# Moter_Control_2021-08-13.net
KiCad netlist of a schematic drawn in Altium Designer
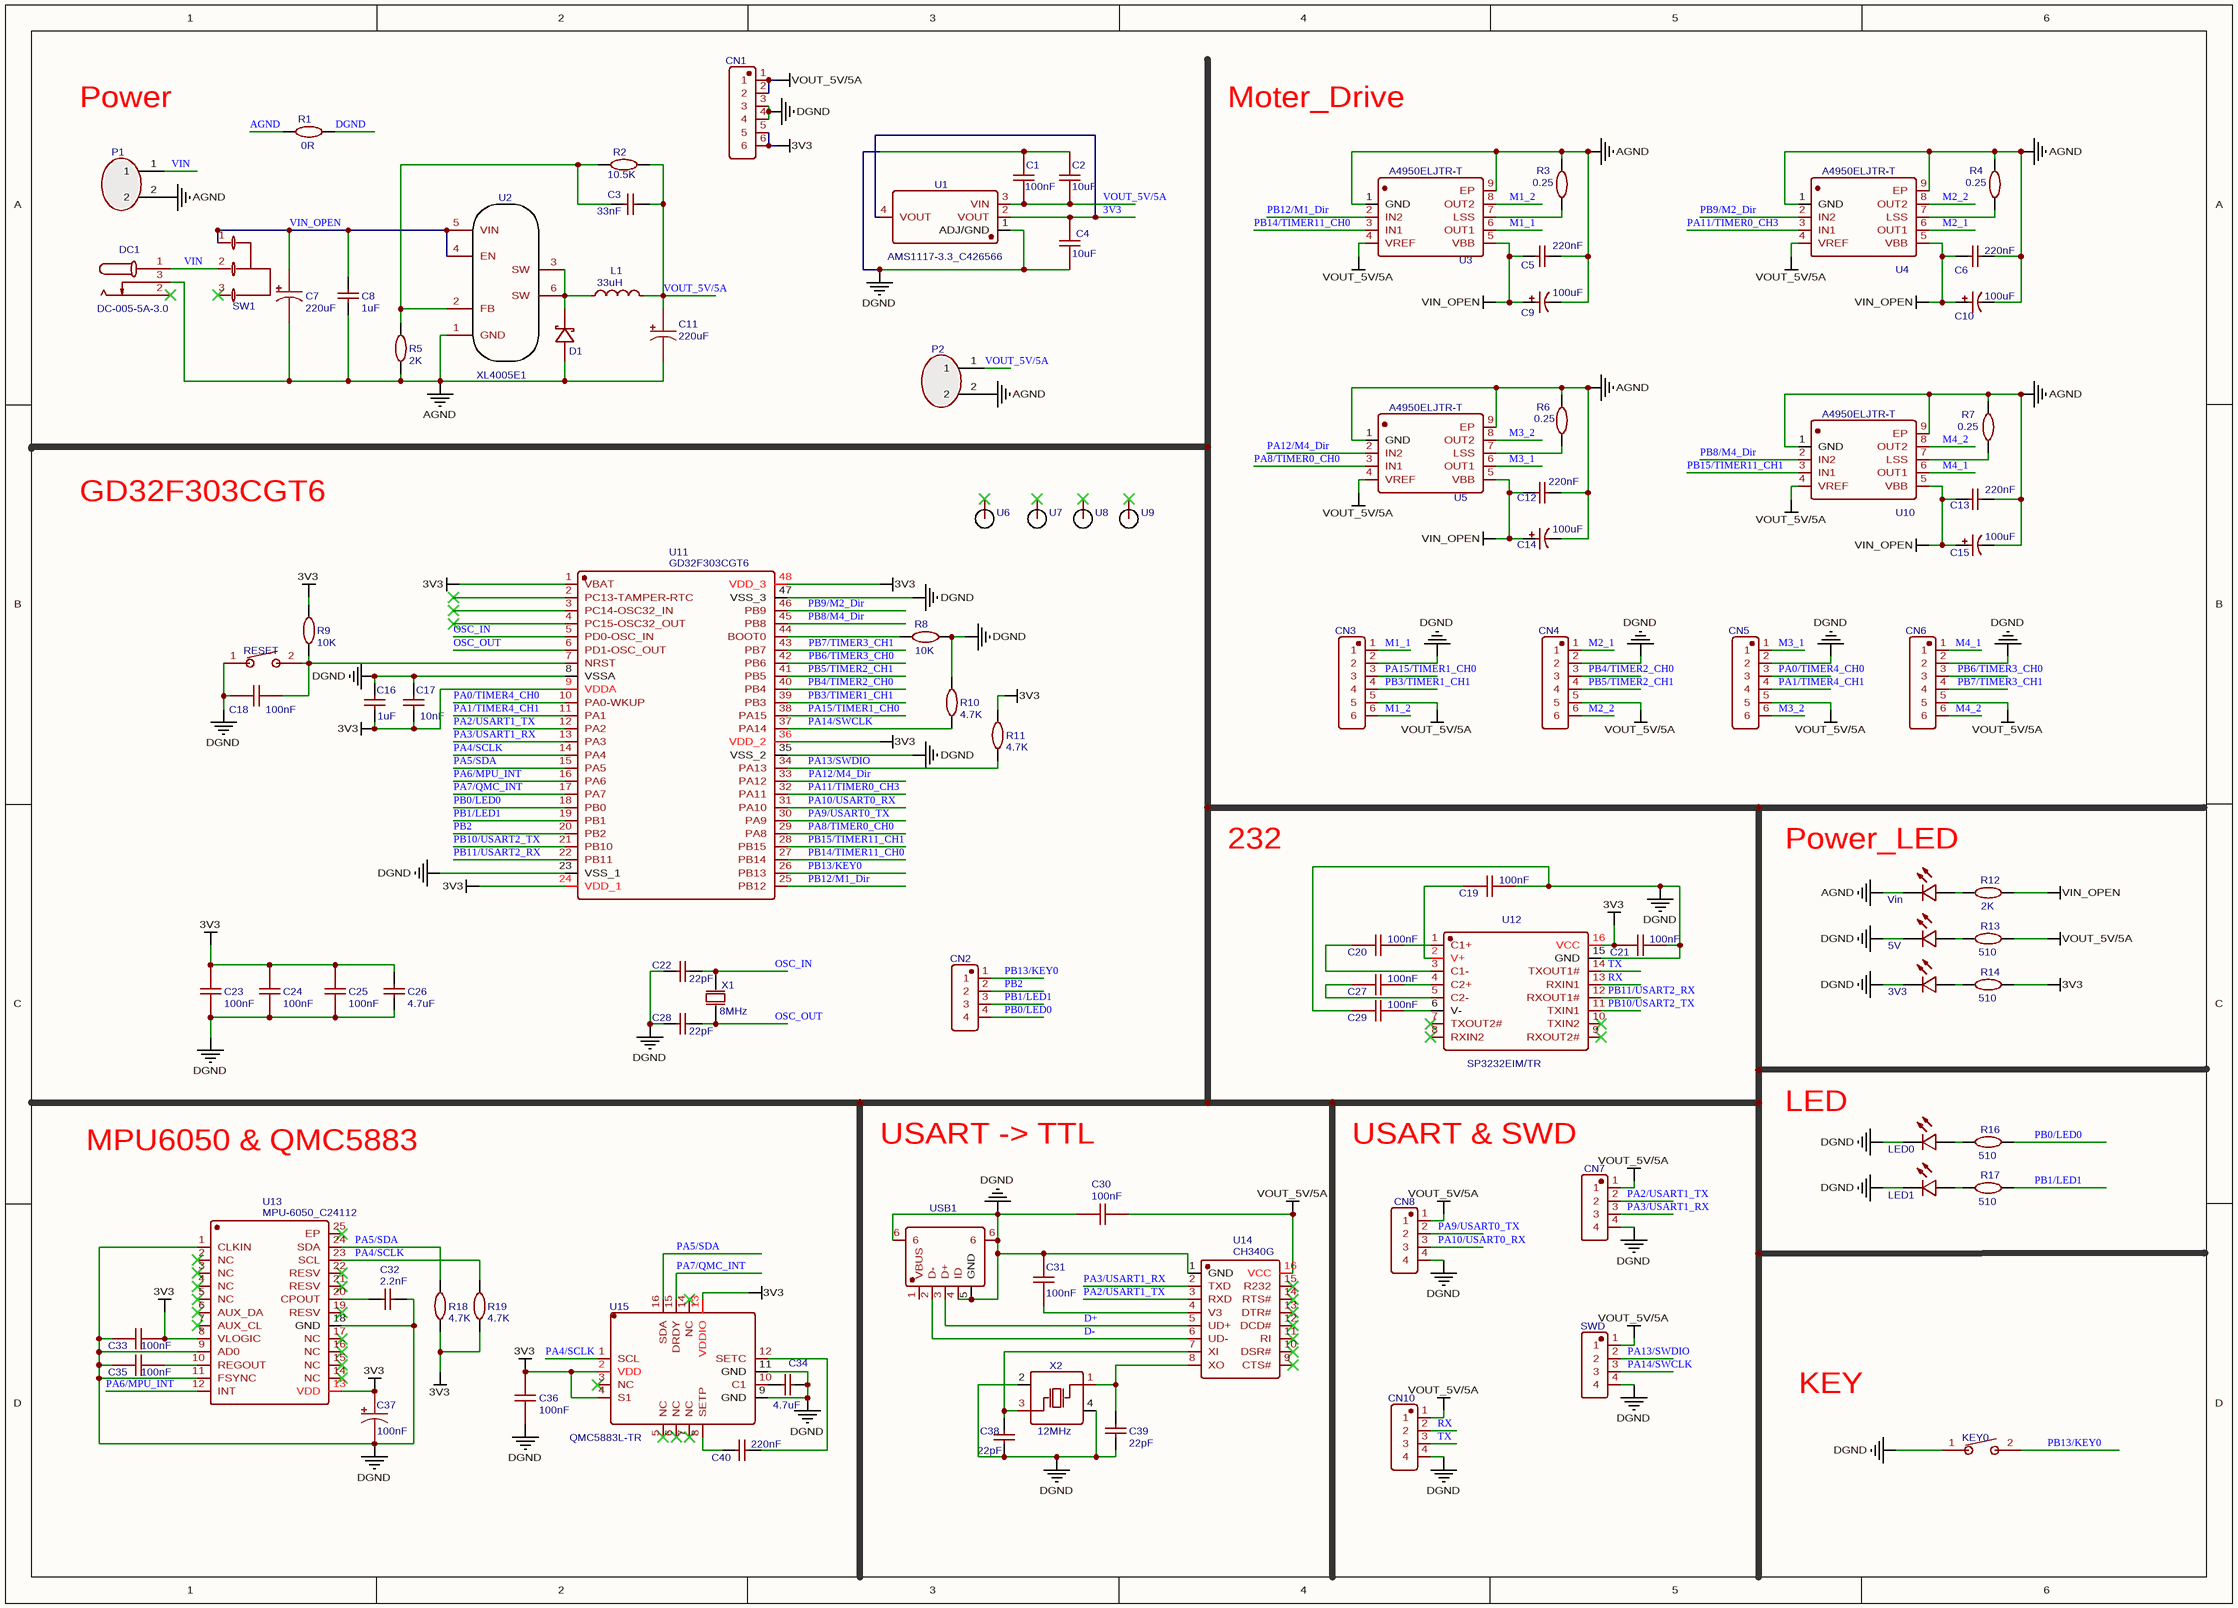
[diagram p0: Moter_Control_2021-08-13.schdoc]

(export (version "E")
  (design (tool "Eeschema 10.0.6"))
  (components
    (comp (ref "3V3")
      (value "19-217/BHC-ZL1M2RY/3T")
      (footprint "LED0603_B")
      (fields (field (name "BOM_SUPPLIER PART") "C72041"))
      (libsource (lib "altium-import") (part "root_0_19-217/BHC-ZL1M2RY/3T_"))
    )
    (comp (ref "5V")
      (value "19-217/BHC-ZL1M2RY/3T")
      (footprint "LED0603_B")
      (fields (field (name "BOM_SUPPLIER PART") "C72041"))
      (libsource (lib "altium-import") (part "root_0_19-217/BHC-ZL1M2RY/3T_"))
    )
    (comp (ref "C1")
      (value "100nF")
      (footprint "C0603_L")
      (fields
        (field (name "BOM_MANUFACTURER PART") "CC0603KRX7R9BB104")
        (field (name "BOM_SUPPLIER PART") "C14663")
      )
      (libsource (lib "altium-import") (part "root_1_100nF_"))
    )
    (comp (ref "C2")
      (value "10uF")
      (footprint "C0603_L")
      (fields
        (field (name "BOM_MANUFACTURER PART") "CL10A106MA8NRNC")
        (field (name "BOM_SUPPLIER PART") "C96446")
      )
      (libsource (lib "altium-import") (part "root_1_10uF_"))
    )
    (comp (ref "C3")
      (value "33nF")
      (footprint "C0603_L")
      (fields
        (field (name "BOM_MANUFACTURER PART") "CL10B333KB8NNNC")
        (field (name "BOM_SUPPLIER PART") "C21117")
      )
      (libsource (lib "altium-import") (part "root_0_33nF_"))
    )
    (comp (ref "C4")
      (value "10uF")
      (footprint "C0603_L")
      (fields
        (field (name "BOM_MANUFACTURER PART") "CL10A106MA8NRNC")
        (field (name "BOM_SUPPLIER PART") "C96446")
      )
      (libsource (lib "altium-import") (part "root_1_10uF_"))
    )
    (comp (ref "C5")
      (value "220nF")
      (footprint "C0603_L")
      (fields
        (field (name "BOM_MANUFACTURER PART") "CL10B224KA8NNNC")
        (field (name "BOM_SUPPLIER PART") "C21120")
      )
      (libsource (lib "altium-import") (part "root_2_220nF_"))
    )
    (comp (ref "C6")
      (value "220nF")
      (footprint "C0603_L")
      (fields
        (field (name "BOM_MANUFACTURER PART") "CL10B224KA8NNNC")
        (field (name "BOM_SUPPLIER PART") "C21120")
      )
      (libsource (lib "altium-import") (part "root_2_220nF_"))
    )
    (comp (ref "C7")
      (value "220uF")
      (footprint "CE E(8*10.2)")
      (fields
        (field (name "BOM_MANUFACTURER PART") "RVT1H471M1213")
        (field (name "BOM_SUPPLIER PART") "C90272")
      )
      (libsource (lib "altium-import") (part "root_0_470uF_"))
    )
    (comp (ref "C8")
      (value "1uF")
      (footprint "C0603_L")
      (fields
        (field (name "BOM_MANUFACTURER PART") "CL10A105KB8NNNC")
        (field (name "BOM_SUPPLIER PART") "C15849")
      )
      (libsource (lib "altium-import") (part "root_3_1uF_"))
    )
    (comp (ref "C9")
      (value "100uF")
      (footprint "CE D(6.3*7.7)")
      (fields
        (field (name "BOM_MANUFACTURER PART") "RVT1H101M0810")
        (field (name "BOM_SUPPLIER PART") "C3352")
      )
      (libsource (lib "altium-import") (part "root_0_100uF_"))
    )
    (comp (ref "C10")
      (value "100uF")
      (footprint "CE D(6.3*7.7)")
      (fields
        (field (name "BOM_MANUFACTURER PART") "RVT1H101M0810")
        (field (name "BOM_SUPPLIER PART") "C3352")
      )
      (libsource (lib "altium-import") (part "root_0_100uF_"))
    )
    (comp (ref "C11")
      (value "220uF")
      (footprint "CE E(8*10.2)")
      (fields
        (field (name "BOM_MANUFACTURER PART") "RVT1H471M1213")
        (field (name "BOM_SUPPLIER PART") "C90272")
      )
      (libsource (lib "altium-import") (part "root_0_470uF_"))
    )
    (comp (ref "C12")
      (value "220nF")
      (footprint "C0603_L")
      (fields
        (field (name "BOM_MANUFACTURER PART") "CL10B224KA8NNNC")
        (field (name "BOM_SUPPLIER PART") "C21120")
      )
      (libsource (lib "altium-import") (part "root_2_220nF_"))
    )
    (comp (ref "C13")
      (value "220nF")
      (footprint "C0603_L")
      (fields
        (field (name "BOM_MANUFACTURER PART") "CL10B224KA8NNNC")
        (field (name "BOM_SUPPLIER PART") "C21120")
      )
      (libsource (lib "altium-import") (part "root_2_220nF_"))
    )
    (comp (ref "C14")
      (value "100uF")
      (footprint "CE D(6.3*7.7)")
      (fields
        (field (name "BOM_MANUFACTURER PART") "RVT1H101M0810")
        (field (name "BOM_SUPPLIER PART") "C3352")
      )
      (libsource (lib "altium-import") (part "root_0_100uF_"))
    )
    (comp (ref "C15")
      (value "100uF")
      (footprint "CE D(6.3*7.7)")
      (fields
        (field (name "BOM_MANUFACTURER PART") "RVT1H101M0810")
        (field (name "BOM_SUPPLIER PART") "C3352")
      )
      (libsource (lib "altium-import") (part "root_0_100uF_"))
    )
    (comp (ref "C16")
      (value "1uF")
      (footprint "C0603_L")
      (fields
        (field (name "BOM_MANUFACTURER PART") "CL10A105KB8NNNC")
        (field (name "BOM_SUPPLIER PART") "C15849")
      )
      (libsource (lib "altium-import") (part "root_1_1uF_"))
    )
    (comp (ref "C17")
      (value "10nF")
      (footprint "C0603_L")
      (fields
        (field (name "BOM_MANUFACTURER PART") "0603B103K500NT")
        (field (name "BOM_SUPPLIER PART") "C57112")
      )
      (libsource (lib "altium-import") (part "root_1_10nF_"))
    )
    (comp (ref "C18")
      (value "100nF")
      (footprint "C0603_L")
      (fields
        (field (name "BOM_MANUFACTURER PART") "CC0603KRX7R9BB104")
        (field (name "BOM_SUPPLIER PART") "C14663")
      )
      (libsource (lib "altium-import") (part "root_0_100nF_"))
    )
    (comp (ref "C19")
      (value "100nF")
      (footprint "C0603_L")
      (fields
        (field (name "BOM_MANUFACTURER PART") "CC0603KRX7R9BB104")
        (field (name "BOM_SUPPLIER PART") "C14663")
      )
      (libsource (lib "altium-import") (part "root_2_100nF_"))
    )
    (comp (ref "C20")
      (value "100nF")
      (footprint "C0603_L")
      (fields
        (field (name "BOM_MANUFACTURER PART") "CC0603KRX7R9BB104")
        (field (name "BOM_SUPPLIER PART") "C14663")
      )
      (libsource (lib "altium-import") (part "root_2_100nF_"))
    )
    (comp (ref "C21")
      (value "100nF")
      (footprint "C0603_L")
      (fields
        (field (name "BOM_MANUFACTURER PART") "CC0603KRX7R9BB104")
        (field (name "BOM_SUPPLIER PART") "C14663")
      )
      (libsource (lib "altium-import") (part "root_2_100nF_"))
    )
    (comp (ref "C22")
      (value "22pF")
      (footprint "C0603_L")
      (fields
        (field (name "BOM_MANUFACTURER PART") "CL10C220JB8NNNC")
        (field (name "BOM_SUPPLIER PART") "C1653")
      )
      (libsource (lib "altium-import") (part "root_0_22pF_"))
    )
    (comp (ref "C23")
      (value "100nF")
      (footprint "C0603_L")
      (fields
        (field (name "BOM_MANUFACTURER PART") "CC0603KRX7R9BB104")
        (field (name "BOM_SUPPLIER PART") "C14663")
      )
      (libsource (lib "altium-import") (part "root_1_100nF_"))
    )
    (comp (ref "C24")
      (value "100nF")
      (footprint "C0603_L")
      (fields
        (field (name "BOM_MANUFACTURER PART") "CC0603KRX7R9BB104")
        (field (name "BOM_SUPPLIER PART") "C14663")
      )
      (libsource (lib "altium-import") (part "root_1_100nF_"))
    )
    (comp (ref "C25")
      (value "100nF")
      (footprint "C0603_L")
      (fields
        (field (name "BOM_MANUFACTURER PART") "CC0603KRX7R9BB104")
        (field (name "BOM_SUPPLIER PART") "C14663")
      )
      (libsource (lib "altium-import") (part "root_1_100nF_"))
    )
    (comp (ref "C26")
      (value "4.7uF")
      (footprint "C0603_L")
      (fields
        (field (name "BOM_MANUFACTURER PART") "CL10A475KO8NNNC")
        (field (name "BOM_SUPPLIER PART") "C19666")
      )
      (libsource (lib "altium-import") (part "root_1_4.7uF_"))
    )
    (comp (ref "C27")
      (value "100nF")
      (footprint "C0603_L")
      (fields
        (field (name "BOM_MANUFACTURER PART") "CC0603KRX7R9BB104")
        (field (name "BOM_SUPPLIER PART") "C14663")
      )
      (libsource (lib "altium-import") (part "root_2_100nF_"))
    )
    (comp (ref "C28")
      (value "22pF")
      (footprint "C0603_L")
      (fields
        (field (name "BOM_MANUFACTURER PART") "CL10C220JB8NNNC")
        (field (name "BOM_SUPPLIER PART") "C1653")
      )
      (libsource (lib "altium-import") (part "root_0_22pF_"))
    )
    (comp (ref "C29")
      (value "100nF")
      (footprint "C0603_L")
      (fields
        (field (name "BOM_MANUFACTURER PART") "CC0603KRX7R9BB104")
        (field (name "BOM_SUPPLIER PART") "C14663")
      )
      (libsource (lib "altium-import") (part "root_2_100nF_"))
    )
    (comp (ref "C30")
      (value "100nF")
      (footprint "C0603_L")
      (fields
        (field (name "BOM_MANUFACTURER PART") "CC0603KRX7R9BB104")
        (field (name "BOM_SUPPLIER PART") "C14663")
      )
      (libsource (lib "altium-import") (part "root_2_100nF_"))
    )
    (comp (ref "C31")
      (value "100nF")
      (footprint "C0603_L")
      (fields
        (field (name "BOM_MANUFACTURER PART") "CC0603KRX7R9BB104")
        (field (name "BOM_SUPPLIER PART") "C14663")
      )
      (libsource (lib "altium-import") (part "root_1_100nF_"))
    )
    (comp (ref "C32")
      (value "2.2nF")
      (footprint "C0603_L")
      (fields
        (field (name "BOM_MANUFACTURER PART") "0603B222K500NT")
        (field (name "BOM_SUPPLIER PART") "C1604")
      )
      (libsource (lib "altium-import") (part "root_0_2.2nF_"))
    )
    (comp (ref "C33")
      (value "100nF")
      (footprint "C0603_L")
      (fields
        (field (name "BOM_MANUFACTURER PART") "CC0603KRX7R9BB104")
        (field (name "BOM_SUPPLIER PART") "C14663")
      )
      (libsource (lib "altium-import") (part "root_0_100nF_"))
    )
    (comp (ref "C34")
      (value "4.7uF")
      (footprint "C0603_L")
      (fields
        (field (name "BOM_MANUFACTURER PART") "CL10A475KO8NNNC")
        (field (name "BOM_SUPPLIER PART") "C19666")
      )
      (libsource (lib "altium-import") (part "root_0_4.7uF_"))
    )
    (comp (ref "C35")
      (value "100nF")
      (footprint "C0603_L")
      (fields
        (field (name "BOM_MANUFACTURER PART") "CC0603KRX7R9BB104")
        (field (name "BOM_SUPPLIER PART") "C14663")
      )
      (libsource (lib "altium-import") (part "root_0_100nF_"))
    )
    (comp (ref "C36")
      (value "100nF")
      (footprint "C0603_L")
      (fields
        (field (name "BOM_MANUFACTURER PART") "CC0603KRX7R9BB104")
        (field (name "BOM_SUPPLIER PART") "C14663")
      )
      (libsource (lib "altium-import") (part "root_1_100nF_"))
    )
    (comp (ref "C37")
      (value "100nF")
      (footprint "CAP-SMD_L3.2-W1.6-R-RD")
      (fields
        (field (name "BOM_MANUFACTURER PART") "T491A104K035AT")
        (field (name "BOM_SUPPLIER PART") "C122257")
        (field (name "CONTRIBUTOR") "LCSC")
      )
      (libsource (lib "") (part "root_1_100nF__1"))
    )
    (comp (ref "C38")
      (value "22pF")
      (footprint "C0603_L")
      (fields
        (field (name "BOM_MANUFACTURER PART") "CL10C220JB8NNNC")
        (field (name "BOM_SUPPLIER PART") "C1653")
      )
      (libsource (lib "altium-import") (part "root_1_22pF_"))
    )
    (comp (ref "C39")
      (value "22pF")
      (footprint "C0603_L")
      (fields
        (field (name "BOM_MANUFACTURER PART") "CL10C220JB8NNNC")
        (field (name "BOM_SUPPLIER PART") "C1653")
      )
      (libsource (lib "altium-import") (part "root_3_22pF_"))
    )
    (comp (ref "C40")
      (value "220nF")
      (footprint "C0603_L")
      (fields
        (field (name "BOM_MANUFACTURER PART") "CL10B224KA8NNNC")
        (field (name "BOM_SUPPLIER PART") "C21120")
      )
      (libsource (lib "altium-import") (part "root_0_220nF_"))
    )
    (comp (ref "CN1")
      (value "HX25003-6WAP")
      (footprint "Test_2.54_2×3Pin")
      (fields (field (name "BOM_SUPPLIER PART") "C442330") (field (name "CONTRIBUTOR") "LCSC"))
      (libsource (lib "altium-import") (part "root_0_HX25003-6WAP_"))
    )
    (comp (ref "CN2")
      (value "GP26-2520WV-4P")
      (footprint "Test_2.54_4Pin")
      (fields (field (name "BOM_SUPPLIER PART") "C2681739") (field (name "CONTRIBUTOR") "LCSC"))
      (libsource (lib "altium-import") (part "root_0_GP26-2520WV-4P_"))
    )
    (comp (ref "CN3")
      (value "HX25003-6WAP")
      (footprint "XH2.54-WI-6P")
      (fields (field (name "BOM_SUPPLIER PART") "C442330") (field (name "CONTRIBUTOR") "LCSC"))
      (libsource (lib "altium-import") (part "root_0_HX25003-6WAP_"))
    )
    (comp (ref "CN4")
      (value "HX25003-6WAP")
      (footprint "XH2.54-WI-6P")
      (fields (field (name "BOM_SUPPLIER PART") "C442330") (field (name "CONTRIBUTOR") "LCSC"))
      (libsource (lib "altium-import") (part "root_0_HX25003-6WAP_"))
    )
    (comp (ref "CN5")
      (value "HX25003-6WAP")
      (footprint "XH2.54-WI-6P")
      (fields (field (name "BOM_SUPPLIER PART") "C442330") (field (name "CONTRIBUTOR") "LCSC"))
      (libsource (lib "altium-import") (part "root_0_HX25003-6WAP_"))
    )
    (comp (ref "CN6")
      (value "HX25003-6WAP")
      (footprint "XH2.54-WI-6P")
      (fields (field (name "BOM_SUPPLIER PART") "C442330") (field (name "CONTRIBUTOR") "LCSC"))
      (libsource (lib "altium-import") (part "root_0_HX25003-6WAP_"))
    )
    (comp (ref "CN7")
      (value "HX25035-4WAP")
      (footprint "Test_2.54_4Pin")
      (fields (field (name "BOM_SUPPLIER PART") "C442385") (field (name "CONTRIBUTOR") "LCSC"))
      (libsource (lib "altium-import") (part "root_0_HX25035-4WAP_"))
    )
    (comp (ref "CN8")
      (value "HX25035-4WAP")
      (footprint "XH2.54-WI-4P")
      (fields (field (name "BOM_SUPPLIER PART") "C442385") (field (name "CONTRIBUTOR") "LCSC"))
      (libsource (lib "altium-import") (part "root_0_HX25035-4WAP_"))
    )
    (comp (ref "CN10")
      (value "HX25035-4WAP")
      (footprint "XH2.54-WI-4P")
      (fields (field (name "BOM_SUPPLIER PART") "C442385") (field (name "CONTRIBUTOR") "LCSC"))
      (libsource (lib "altium-import") (part "root_0_HX25035-4WAP_"))
    )
    (comp (ref "D1")
      (value "SS54_C727065")
      (footprint "SMA_L4.3-W2.6-LS5.0-RD")
      (fields
        (field (name "BOM_SUPPLIER PART") "C727065")
        (field (name "BOM_MANUFACTURER PART") "SS54")
        (field (name "CONTRIBUTOR") "LCSC")
      )
      (libsource (lib "altium-import") (part "root_3_SS54_C727065_"))
    )
    (comp (ref "DC1")
      (value "DC-005-5A-3.0")
      (footprint "DC-IN-TH_DC-005-5A-3.0")
      (fields (field (name "BOM_SUPPLIER PART") "C388625") (field (name "CONTRIBUTOR") "LCSC"))
      (libsource (lib "altium-import") (part "root_0_DC-005-5A-3.0_"))
    )
    (comp (ref "KEY0")
      (value "TSA363G25-250B")
      (footprint "SW-SMD_L6.5-W3.6-LS8.0")
      (fields (field (name "BOM_SUPPLIER PART") "C354943") (field (name "CONTRIBUTOR") "LCSC"))
      (libsource (lib "altium-import") (part "root_0_TSA363G25-250B_"))
    )
    (comp (ref "L1")
      (value "33uH")
      (footprint "IND-SMD_L13.45-W12.6")
      (fields
        (field (name "BOM_SUPPLIER PART") "C408530")
        (field (name "BOM_MANUFACTURER PART") "MWSA1206S-330MT")
        (field (name "CONTRIBUTOR") "LCSC")
      )
      (libsource (lib "altium-import") (part "root_0_33uH_"))
    )
    (comp (ref "LED0")
      (value "19-217/BHC-ZL1M2RY/3T")
      (footprint "LED0603_B")
      (fields (field (name "BOM_SUPPLIER PART") "C72041"))
      (libsource (lib "altium-import") (part "root_0_19-217/BHC-ZL1M2RY/3T_"))
    )
    (comp (ref "LED1")
      (value "19-217/BHC-ZL1M2RY/3T")
      (footprint "LED0603_B")
      (fields (field (name "BOM_SUPPLIER PART") "C72041"))
      (libsource (lib "altium-import") (part "root_0_19-217/BHC-ZL1M2RY/3T_"))
    )
    (comp (ref "P1")
      (value "WJ126V-5.0-2P")
      (footprint "HT3.96-WI-2P-ORG")
      (fields (field (name "BOM_SUPPLIER PART") "C8404"))
      (libsource (lib "altium-import") (part "root_0_WJ126V-5.0-2P_"))
    )
    (comp (ref "P2")
      (value "WJ126V-5.0-2P")
      (footprint "HT3.96-WI-2P-ORG")
      (fields (field (name "BOM_SUPPLIER PART") "C8404"))
      (libsource (lib "altium-import") (part "root_0_WJ126V-5.0-2P_"))
    )
    (comp (ref "R1")
      (value "0R")
      (footprint "R0805_L")
      (fields
        (field (name "BOM_MANUFACTURER PART") "0603WAF0000T5E")
        (field (name "BOM_SUPPLIER PART") "C21189")
      )
      (libsource (lib "altium-import") (part "root_0_0R_"))
    )
    (comp (ref "R2")
      (value "10.5K")
      (footprint "R0603_L")
      (fields
        (field (name "BOM_MANUFACTURER PART") "0603WAF1052T5E")
        (field (name "BOM_SUPPLIER PART") "C22855")
      )
      (libsource (lib "altium-import") (part "root_2_10.5K_"))
    )
    (comp (ref "R3")
      (value "0.25")
      (footprint "R2512_L")
      (fields
        (field (name "BOM_MANUFACTURER PART") "25121WF250LT4E")
        (field (name "BOM_SUPPLIER PART") "C25467")
      )
      (libsource (lib "altium-import") (part "root_3_0.25_"))
    )
    (comp (ref "R4")
      (value "0.25")
      (footprint "R2512_L")
      (fields
        (field (name "BOM_MANUFACTURER PART") "25121WF250LT4E")
        (field (name "BOM_SUPPLIER PART") "C25467")
      )
      (libsource (lib "altium-import") (part "root_3_0.25_"))
    )
    (comp (ref "R5")
      (value "2K")
      (footprint "R0603_L")
      (fields
        (field (name "BOM_MANUFACTURER PART") "0603WAF2001T5E")
        (field (name "BOM_SUPPLIER PART") "C22975")
      )
      (libsource (lib "altium-import") (part "root_1_2K_"))
    )
    (comp (ref "R6")
      (value "0.25")
      (footprint "R2512_L")
      (fields
        (field (name "BOM_MANUFACTURER PART") "25121WF250LT4E")
        (field (name "BOM_SUPPLIER PART") "C25467")
      )
      (libsource (lib "altium-import") (part "root_3_0.25_"))
    )
    (comp (ref "R7")
      (value "0.25")
      (footprint "R2512_L")
      (fields
        (field (name "BOM_MANUFACTURER PART") "25121WF250LT4E")
        (field (name "BOM_SUPPLIER PART") "C25467")
      )
      (libsource (lib "altium-import") (part "root_3_0.25_"))
    )
    (comp (ref "R8")
      (value "10K")
      (footprint "R0603_L")
      (fields
        (field (name "BOM_MANUFACTURER PART") "0603WAF1002T5E")
        (field (name "BOM_SUPPLIER PART") "C25804")
      )
      (libsource (lib "altium-import") (part "root_0_10K_"))
    )
    (comp (ref "R9")
      (value "10K")
      (footprint "R0603_L")
      (fields
        (field (name "BOM_MANUFACTURER PART") "0603WAF1002T5E")
        (field (name "BOM_SUPPLIER PART") "C25804")
      )
      (libsource (lib "altium-import") (part "root_1_10K_"))
    )
    (comp (ref "R10")
      (value "4.7K")
      (footprint "R0603_L")
      (fields
        (field (name "BOM_MANUFACTURER PART") "RC0603FR-074K7L")
        (field (name "BOM_SUPPLIER PART") "C99782")
      )
      (libsource (lib "altium-import") (part "root_1_4.7K_"))
    )
    (comp (ref "R11")
      (value "4.7K")
      (footprint "R0603_L")
      (fields
        (field (name "BOM_MANUFACTURER PART") "RC0603FR-074K7L")
        (field (name "BOM_SUPPLIER PART") "C99782")
      )
      (libsource (lib "altium-import") (part "root_1_4.7K_"))
    )
    (comp (ref "R12")
      (value "2K")
      (footprint "R0603_L")
      (fields
        (field (name "BOM_MANUFACTURER PART") "0603WAF2001T5E")
        (field (name "BOM_SUPPLIER PART") "C22975")
      )
      (libsource (lib "altium-import") (part "root_0_2K_"))
    )
    (comp (ref "R13")
      (value "510")
      (footprint "R0603_L")
      (fields
        (field (name "BOM_MANUFACTURER PART") "0603WAF5100T5E")
        (field (name "BOM_SUPPLIER PART") "C23193")
      )
      (libsource (lib "altium-import") (part "root_0_510_"))
    )
    (comp (ref "R14")
      (value "510")
      (footprint "R0603_L")
      (fields
        (field (name "BOM_MANUFACTURER PART") "0603WAF5100T5E")
        (field (name "BOM_SUPPLIER PART") "C23193")
      )
      (libsource (lib "altium-import") (part "root_0_510_"))
    )
    (comp (ref "R16")
      (value "510")
      (footprint "R0603_L")
      (fields
        (field (name "BOM_MANUFACTURER PART") "0603WAF5100T5E")
        (field (name "BOM_SUPPLIER PART") "C23193")
      )
      (libsource (lib "altium-import") (part "root_0_510_"))
    )
    (comp (ref "R17")
      (value "510")
      (footprint "R0603_L")
      (fields
        (field (name "BOM_MANUFACTURER PART") "0603WAF5100T5E")
        (field (name "BOM_SUPPLIER PART") "C23193")
      )
      (libsource (lib "altium-import") (part "root_0_510_"))
    )
    (comp (ref "R18")
      (value "4.7K")
      (footprint "R0603_L")
      (fields
        (field (name "BOM_MANUFACTURER PART") "0603WAF4701T5E")
        (field (name "BOM_SUPPLIER PART") "C23162")
      )
      (libsource (lib "altium-import") (part "root_1_4.7K_"))
    )
    (comp (ref "R19")
      (value "4.7K")
      (footprint "R0603_L")
      (fields
        (field (name "BOM_MANUFACTURER PART") "0603WAF4701T5E")
        (field (name "BOM_SUPPLIER PART") "C23162")
      )
      (libsource (lib "altium-import") (part "root_1_4.7K_"))
    )
    (comp (ref "RESET")
      (value "TSA363G25-250B")
      (footprint "SW-SMD_L6.5-W3.6-LS8.0")
      (fields (field (name "BOM_SUPPLIER PART") "C354943") (field (name "CONTRIBUTOR") "LCSC"))
      (libsource (lib "altium-import") (part "root_0_TSA363G25-250B_"))
    )
    (comp (ref "SW1")
      (value "SS-12D06L5")
      (footprint "SS-12D10")
      (fields (field (name "BOM_SUPPLIER PART") "C319015") (field (name "CONTRIBUTOR") "LCSC"))
      (libsource (lib "altium-import") (part "root_3_mirrored_SS-12D06L5_"))
    )
    (comp (ref "SWD")
      (value "HX25035-4WAP")
      (footprint "Test_2.54_4Pin")
      (fields (field (name "BOM_SUPPLIER PART") "C442385") (field (name "CONTRIBUTOR") "LCSC"))
      (libsource (lib "altium-import") (part "root_0_HX25035-4WAP_"))
    )
    (comp (ref "U1")
      (value "AMS1117-3.3_C426566")
      (footprint "SOT-223_L6.5-W3.5-P2.30-LS7.0-BR")
      (fields
        (field (name "BOM_SUPPLIER PART") "C426566")
        (field (name "BOM_MANUFACTURER PART") "AMS1117-3.3")
        (field (name "CONTRIBUTOR") "LCSC")
      )
      (libsource (lib "altium-import") (part "root_2_AMS1117-3.3_C426566_"))
    )
    (comp (ref "U2")
      (value "XL4005E1")
      (footprint "TO-263-5_L10.2-W9.2-P1.70-TL")
      (fields (field (name "BOM_SUPPLIER PART") "C73332"))
      (libsource (lib "altium-import") (part "root_0_XL4005E1_"))
    )
    (comp (ref "U3")
      (value "A4950ELJTR-T")
      (footprint "A4950")
      (fields (field (name "BOM_SUPPLIER PART") "C82404"))
      (libsource (lib "altium-import") (part "root_0_A4950ELJTR-T_"))
    )
    (comp (ref "U4")
      (value "A4950ELJTR-T")
      (footprint "A4950")
      (fields (field (name "BOM_SUPPLIER PART") "C82404"))
      (libsource (lib "altium-import") (part "root_0_A4950ELJTR-T_"))
    )
    (comp (ref "U5")
      (value "A4950ELJTR-T")
      (footprint "A4950")
      (fields (field (name "BOM_SUPPLIER PART") "C82404"))
      (libsource (lib "altium-import") (part "root_0_A4950ELJTR-T_"))
    )
    (comp (ref "U6")
      (value "Fix")
      (footprint "FIX")
      (fields (field (name "CONTRIBUTOR") "xdyewu"))
      (libsource (lib "altium-import") (part "root_0_Fix_"))
    )
    (comp (ref "U7")
      (value "Fix")
      (footprint "FIX")
      (fields (field (name "CONTRIBUTOR") "xdyewu"))
      (libsource (lib "altium-import") (part "root_0_Fix_"))
    )
    (comp (ref "U8")
      (value "Fix")
      (footprint "FIX")
      (fields (field (name "CONTRIBUTOR") "xdyewu"))
      (libsource (lib "altium-import") (part "root_0_Fix_"))
    )
    (comp (ref "U9")
      (value "Fix")
      (footprint "FIX")
      (fields (field (name "CONTRIBUTOR") "xdyewu"))
      (libsource (lib "altium-import") (part "root_0_Fix_"))
    )
    (comp (ref "U10")
      (value "A4950ELJTR-T")
      (footprint "A4950")
      (fields (field (name "BOM_SUPPLIER PART") "C82404"))
      (libsource (lib "altium-import") (part "root_0_A4950ELJTR-T_"))
    )
    (comp (ref "U11")
      (value "GD32F303CGT6")
      (footprint "Moter_Control_2021-08-13:LQFP-48_L7.0-W7.0-P0.50-LS9.0-BL")
      (fields (field (name "BOM_SUPPLIER PART") "C2835084") (field (name "CONTRIBUTOR") "LCSC"))
      (libsource (lib "altium-import") (part "root_0_GD32F303CGT6_"))
    )
    (comp (ref "U12")
      (value "SP3232EIM/TR")
      (footprint "SOP-16_L10.0-W3.9-P1.27-LS6.0-BL")
      (fields (field (name "BOM_SUPPLIER PART") "C519088") (field (name "CONTRIBUTOR") "LCSC"))
      (libsource (lib "altium-import") (part "root_0_SP3232EIM/TR_"))
    )
    (comp (ref "U13")
      (value "MPU-6050_C24112")
      (footprint "QFN-24_L4.0-W4.0-P0.50-BL-EP2.6")
      (fields (field (name "BOM_MANUFACTURER PART") "MPU-6050") (field (name "BOM_SUPPLIER PART") "C24112"))
      (libsource (lib "altium-import") (part "root_0_MPU-6050_C24112_"))
    )
    (comp (ref "U14")
      (value "CH340G")
      (footprint "SOIC-16_L9.9-W3.9-P1.27-LS6.0-BR")
      (fields (field (name "BOM_SUPPLIER PART") "C14267"))
      (libsource (lib "altium-import") (part "root_0_CH340G_"))
    )
    (comp (ref "U15")
      (value "QMC5883L-TR")
      (footprint "SENSOR-SMD_QMC5883L-TR")
      (fields (field (name "BOM_SUPPLIER PART") "C192585") (field (name "CONTRIBUTOR") "LCSC"))
      (libsource (lib "altium-import") (part "root_0_QMC5883L-TR_"))
    )
    (comp (ref "USB1")
      (value "U-M-M5DS-W-5_C2689963")
      (footprint "USB-MICRO_D")
      (fields
        (field (name "BOM_SUPPLIER PART") "C2689963")
        (field (name "BOM_MANUFACTURER PART") "U-M-M5DS-W-5")
        (field (name "CONTRIBUTOR") "LCSC")
      )
      (libsource (lib "altium-import") (part "root_1_U-M-M5DS-W-5_C2689963_"))
    )
    (comp (ref "Vin")
      (value "19-217/BHC-ZL1M2RY/3T")
      (footprint "LED0603_B")
      (fields (field (name "BOM_SUPPLIER PART") "C72041"))
      (libsource (lib "altium-import") (part "root_0_19-217/BHC-ZL1M2RY/3T_"))
    )
    (comp (ref "X1")
      (value "8MHz")
      (footprint "OSC 5032-2P-Black")
      (fields
        (field (name "BOM_MANUFACTURER PART") "X50328MSB2GI")
        (field (name "BOM_SUPPLIER PART") "C115962")
      )
      (libsource (lib "altium-import") (part "root_1_8MHz_"))
    )
    (comp (ref "X2")
      (value "12MHz")
      (footprint "OSC 3225-4P")
      (fields
        (field (name "BOM_MANUFACTURER PART") "X322512MSB4SI")
        (field (name "BOM_SUPPLIER PART") "C9002")
      )
      (libsource (lib "altium-import") (part "root_2_12MHz_"))
    )
  )
  (nets
    (net (code "1") (name "/D+") (class "Default")
      (node (ref "U14") (pin "5") (pinfunction "UD+_5") (pintype "passive"))
      (node (ref "USB1") (pin "3") (pinfunction "D+_3") (pintype "passive"))
    )
    (net (code "2") (name "/D-") (class "Default")
      (node (ref "U14") (pin "6") (pinfunction "UD-_6") (pintype "passive"))
      (node (ref "USB1") (pin "2") (pinfunction "D-_2") (pintype "passive"))
    )
    (net (code "3") (name "/M1_1") (class "Default")
      (node (ref "CN3") (pin "1") (pinfunction "1_1") (pintype "passive"))
      (node (ref "U3") (pin "6") (pinfunction "OUT1_6") (pintype "passive"))
    )
    (net (code "4") (name "/M1_2") (class "Default")
      (node (ref "CN3") (pin "6") (pinfunction "6_6") (pintype "passive"))
      (node (ref "U3") (pin "8") (pinfunction "OUT2_8") (pintype "passive"))
    )
    (net (code "5") (name "/M2_1") (class "Default")
      (node (ref "CN4") (pin "1") (pinfunction "1_1") (pintype "passive"))
      (node (ref "U4") (pin "6") (pinfunction "OUT1_6") (pintype "passive"))
    )
    (net (code "6") (name "/M2_2") (class "Default")
      (node (ref "CN4") (pin "6") (pinfunction "6_6") (pintype "passive"))
      (node (ref "U4") (pin "8") (pinfunction "OUT2_8") (pintype "passive"))
    )
    (net (code "7") (name "/M3_1") (class "Default")
      (node (ref "CN5") (pin "1") (pinfunction "1_1") (pintype "passive"))
      (node (ref "U5") (pin "6") (pinfunction "OUT1_6") (pintype "passive"))
    )
    (net (code "8") (name "/M3_2") (class "Default")
      (node (ref "CN5") (pin "6") (pinfunction "6_6") (pintype "passive"))
      (node (ref "U5") (pin "8") (pinfunction "OUT2_8") (pintype "passive"))
    )
    (net (code "9") (name "/M4_1") (class "Default")
      (node (ref "CN6") (pin "1") (pinfunction "1_1") (pintype "passive"))
      (node (ref "U10") (pin "6") (pinfunction "OUT1_6") (pintype "passive"))
    )
    (net (code "10") (name "/M4_2") (class "Default")
      (node (ref "CN6") (pin "6") (pinfunction "6_6") (pintype "passive"))
      (node (ref "U10") (pin "8") (pinfunction "OUT2_8") (pintype "passive"))
    )
    (net (code "11") (name "/OSC_IN") (class "Default")
      (node (ref "C22") (pin "2") (pinfunction "2_2") (pintype "passive"))
      (node (ref "U11") (pin "5") (pinfunction "PD0-OSC_IN_5") (pintype "passive"))
      (node (ref "X1") (pin "2") (pinfunction "OSC2_2") (pintype "passive"))
    )
    (net (code "12") (name "/OSC_OUT") (class "Default")
      (node (ref "C28") (pin "2") (pinfunction "2_2") (pintype "passive"))
      (node (ref "U11") (pin "6") (pinfunction "PD1-OSC_OUT_6") (pintype "passive"))
      (node (ref "X1") (pin "1") (pinfunction "OSC1_1") (pintype "passive"))
    )
    (net (code "13") (name "/PA0{slash}TIMER4_CH0") (class "Default")
      (node (ref "CN5") (pin "3") (pinfunction "3_3") (pintype "passive"))
      (node (ref "U11") (pin "10") (pinfunction "PA0-WKUP_10") (pintype "passive"))
    )
    (net (code "14") (name "/PA1{slash}TIMER4_CH1") (class "Default")
      (node (ref "CN5") (pin "4") (pinfunction "4_4") (pintype "passive"))
      (node (ref "U11") (pin "11") (pinfunction "PA1_11") (pintype "passive"))
    )
    (net (code "15") (name "/PA2{slash}USART1_TX") (class "Default")
      (node (ref "CN7") (pin "2") (pinfunction "2_2") (pintype "passive"))
      (node (ref "U11") (pin "12") (pinfunction "PA2_12") (pintype "passive"))
      (node (ref "U14") (pin "3") (pinfunction "RXD_3") (pintype "passive"))
    )
    (net (code "16") (name "/PA3{slash}USART1_RX") (class "Default")
      (node (ref "CN7") (pin "3") (pinfunction "3_3") (pintype "passive"))
      (node (ref "U11") (pin "13") (pinfunction "PA3_13") (pintype "passive"))
      (node (ref "U14") (pin "2") (pinfunction "TXD_2") (pintype "passive"))
    )
    (net (code "17") (name "/PA4{slash}SCLK") (class "Default")
      (node (ref "R19") (pin "2") (pinfunction "2_2") (pintype "passive"))
      (node (ref "U11") (pin "14") (pinfunction "PA4_14") (pintype "passive"))
      (node (ref "U13") (pin "23") (pinfunction "SCL_23") (pintype "passive"))
      (node (ref "U15") (pin "1") (pinfunction "SCL_1") (pintype "passive"))
    )
    (net (code "18") (name "/PA5{slash}SDA") (class "Default")
      (node (ref "R18") (pin "2") (pinfunction "2_2") (pintype "passive"))
      (node (ref "U11") (pin "15") (pinfunction "PA5_15") (pintype "passive"))
      (node (ref "U13") (pin "24") (pinfunction "SDA_24") (pintype "passive"))
      (node (ref "U15") (pin "16") (pinfunction "SDA_16") (pintype "passive"))
    )
    (net (code "19") (name "/PA6{slash}MPU_INT") (class "Default")
      (node (ref "U11") (pin "16") (pinfunction "PA6_16") (pintype "passive"))
      (node (ref "U13") (pin "12") (pinfunction "INT_12") (pintype "passive"))
    )
    (net (code "20") (name "/PA7{slash}QMC_INT") (class "Default")
      (node (ref "U11") (pin "17") (pinfunction "PA7_17") (pintype "passive"))
      (node (ref "U15") (pin "15") (pinfunction "DRDY_15") (pintype "passive"))
    )
    (net (code "21") (name "/PA8{slash}TIMER0_CH0") (class "Default")
      (node (ref "U11") (pin "29") (pinfunction "PA8_29") (pintype "passive"))
      (node (ref "U5") (pin "3") (pinfunction "IN1_3") (pintype "passive"))
    )
    (net (code "22") (name "/PA9{slash}USART0_TX") (class "Default")
      (node (ref "CN8") (pin "2") (pinfunction "2_2") (pintype "passive"))
      (node (ref "U11") (pin "30") (pinfunction "PA9_30") (pintype "passive"))
    )
    (net (code "23") (name "/PA10{slash}USART0_RX") (class "Default")
      (node (ref "CN8") (pin "3") (pinfunction "3_3") (pintype "passive"))
      (node (ref "U11") (pin "31") (pinfunction "PA10_31") (pintype "passive"))
    )
    (net (code "24") (name "/PA11{slash}TIMER0_CH3") (class "Default")
      (node (ref "U11") (pin "32") (pinfunction "PA11_32") (pintype "passive"))
      (node (ref "U4") (pin "3") (pinfunction "IN1_3") (pintype "passive"))
    )
    (net (code "25") (name "/PA12{slash}M4_Dir") (class "Default")
      (node (ref "U11") (pin "33") (pinfunction "PA12_33") (pintype "passive"))
      (node (ref "U5") (pin "2") (pinfunction "IN2_2") (pintype "passive"))
    )
    (net (code "26") (name "/PA13{slash}SWDIO") (class "Default")
      (node (ref "R11") (pin "1") (pinfunction "1_1") (pintype "passive"))
      (node (ref "SWD") (pin "2") (pinfunction "2_2") (pintype "passive"))
      (node (ref "U11") (pin "34") (pinfunction "PA13_34") (pintype "passive"))
    )
    (net (code "27") (name "/PA14{slash}SWCLK") (class "Default")
      (node (ref "R10") (pin "1") (pinfunction "1_1") (pintype "passive"))
      (node (ref "SWD") (pin "3") (pinfunction "3_3") (pintype "passive"))
      (node (ref "U11") (pin "37") (pinfunction "PA14_37") (pintype "passive"))
    )
    (net (code "28") (name "/PA15{slash}TIMER1_CH0") (class "Default")
      (node (ref "CN3") (pin "3") (pinfunction "3_3") (pintype "passive"))
      (node (ref "U11") (pin "38") (pinfunction "PA15_38") (pintype "passive"))
    )
    (net (code "29") (name "/PB0{slash}LED0") (class "Default")
      (node (ref "CN2") (pin "4") (pinfunction "4_4") (pintype "passive"))
      (node (ref "R16") (pin "2") (pinfunction "2_2") (pintype "passive"))
      (node (ref "U11") (pin "18") (pinfunction "PB0_18") (pintype "passive"))
    )
    (net (code "30") (name "/PB1{slash}LED1") (class "Default")
      (node (ref "CN2") (pin "3") (pinfunction "3_3") (pintype "passive"))
      (node (ref "R17") (pin "2") (pinfunction "2_2") (pintype "passive"))
      (node (ref "U11") (pin "19") (pinfunction "PB1_19") (pintype "passive"))
    )
    (net (code "31") (name "/PB2") (class "Default")
      (node (ref "CN2") (pin "2") (pinfunction "2_2") (pintype "passive"))
      (node (ref "U11") (pin "20") (pinfunction "PB2_20") (pintype "passive"))
    )
    (net (code "32") (name "/PB3{slash}TIMER1_CH1") (class "Default")
      (node (ref "CN3") (pin "4") (pinfunction "4_4") (pintype "passive"))
      (node (ref "U11") (pin "39") (pinfunction "PB3_39") (pintype "passive"))
    )
    (net (code "33") (name "/PB4{slash}TIMER2_CH0") (class "Default")
      (node (ref "CN4") (pin "3") (pinfunction "3_3") (pintype "passive"))
      (node (ref "U11") (pin "40") (pinfunction "PB4_40") (pintype "passive"))
    )
    (net (code "34") (name "/PB5{slash}TIMER2_CH1") (class "Default")
      (node (ref "CN4") (pin "4") (pinfunction "4_4") (pintype "passive"))
      (node (ref "U11") (pin "41") (pinfunction "PB5_41") (pintype "passive"))
    )
    (net (code "35") (name "/PB6{slash}TIMER3_CH0") (class "Default")
      (node (ref "CN6") (pin "3") (pinfunction "3_3") (pintype "passive"))
      (node (ref "U11") (pin "42") (pinfunction "PB6_42") (pintype "passive"))
    )
    (net (code "36") (name "/PB7{slash}TIMER3_CH1") (class "Default")
      (node (ref "CN6") (pin "4") (pinfunction "4_4") (pintype "passive"))
      (node (ref "U11") (pin "43") (pinfunction "PB7_43") (pintype "passive"))
    )
    (net (code "37") (name "/PB8{slash}M4_Dir") (class "Default")
      (node (ref "U10") (pin "2") (pinfunction "IN2_2") (pintype "passive"))
      (node (ref "U11") (pin "45") (pinfunction "PB8_45") (pintype "passive"))
    )
    (net (code "38") (name "/PB9{slash}M2_Dir") (class "Default")
      (node (ref "U11") (pin "46") (pinfunction "PB9_46") (pintype "passive"))
      (node (ref "U4") (pin "2") (pinfunction "IN2_2") (pintype "passive"))
    )
    (net (code "39") (name "/PB10{slash}USART2_TX") (class "Default")
      (node (ref "U11") (pin "21") (pinfunction "PB10_21") (pintype "passive"))
      (node (ref "U12") (pin "11") (pinfunction "TXIN1_11") (pintype "passive"))
    )
    (net (code "40") (name "/PB11{slash}USART2_RX") (class "Default")
      (node (ref "U11") (pin "22") (pinfunction "PB11_22") (pintype "passive"))
      (node (ref "U12") (pin "12") (pinfunction "RXOUT1#_12") (pintype "passive"))
    )
    (net (code "41") (name "/PB12{slash}M1_Dir") (class "Default")
      (node (ref "U11") (pin "25") (pinfunction "PB12_25") (pintype "passive"))
      (node (ref "U3") (pin "2") (pinfunction "IN2_2") (pintype "passive"))
    )
    (net (code "42") (name "/PB13{slash}KEY0") (class "Default")
      (node (ref "CN2") (pin "1") (pinfunction "1_1") (pintype "passive"))
      (node (ref "KEY0") (pin "2") (pinfunction "2_2") (pintype "passive"))
      (node (ref "U11") (pin "26") (pinfunction "PB13_26") (pintype "passive"))
    )
    (net (code "43") (name "/PB14{slash}TIMER11_CH0") (class "Default")
      (node (ref "U11") (pin "27") (pinfunction "PB14_27") (pintype "passive"))
      (node (ref "U3") (pin "3") (pinfunction "IN1_3") (pintype "passive"))
    )
    (net (code "44") (name "/PB15{slash}TIMER11_CH1") (class "Default")
      (node (ref "U10") (pin "3") (pinfunction "IN1_3") (pintype "passive"))
      (node (ref "U11") (pin "28") (pinfunction "PB15_28") (pintype "passive"))
    )
    (net (code "45") (name "/RX") (class "Default")
      (node (ref "CN10") (pin "2") (pinfunction "2_2") (pintype "passive"))
      (node (ref "U12") (pin "13") (pinfunction "RXIN1_13") (pintype "passive"))
    )
    (net (code "46") (name "/TX") (class "Default")
      (node (ref "CN10") (pin "3") (pinfunction "3_3") (pintype "passive"))
      (node (ref "U12") (pin "14") (pinfunction "TXOUT1#_14") (pintype "passive"))
    )
    (net (code "47") (name "/VIN") (class "Default")
      (node (ref "DC1") (pin "1") (pinfunction "1_1") (pintype "passive"))
      (node (ref "P1") (pin "1") (pinfunction "1_1") (pintype "passive"))
      (node (ref "SW1") (pin "2") (pinfunction "2_2") (pintype "passive"))
    )
    (net (code "48") (name "3V3") (class "Default")
      (node (ref "C16") (pin "1") (pinfunction "1_1") (pintype "passive"))
      (node (ref "C17") (pin "1") (pinfunction "1_1") (pintype "passive"))
      (node (ref "C21") (pin "2") (pinfunction "2_2") (pintype "passive"))
      (node (ref "C23") (pin "2") (pinfunction "2_2") (pintype "passive"))
      (node (ref "C24") (pin "2") (pinfunction "2_2") (pintype "passive"))
      (node (ref "C25") (pin "2") (pinfunction "2_2") (pintype "passive"))
      (node (ref "C26") (pin "2") (pinfunction "2_2") (pintype "passive"))
      (node (ref "C33") (pin "2") (pinfunction "2_2") (pintype "passive"))
      (node (ref "C36") (pin "2") (pinfunction "2_2") (pintype "passive"))
      (node (ref "C37") (pin "1") (pinfunction "1_1") (pintype "passive"))
      (node (ref "C4") (pin "2") (pinfunction "2_2") (pintype "passive"))
      (node (ref "CN1") (pin "5") (pinfunction "5_5") (pintype "passive"))
      (node (ref "CN1") (pin "6") (pinfunction "6_6") (pintype "passive"))
      (node (ref "R11") (pin "2") (pinfunction "2_2") (pintype "passive"))
      (node (ref "R14") (pin "2") (pinfunction "2_2") (pintype "passive"))
      (node (ref "R18") (pin "1") (pinfunction "1_1") (pintype "passive"))
      (node (ref "R19") (pin "1") (pinfunction "1_1") (pintype "passive"))
      (node (ref "R9") (pin "2") (pinfunction "2_2") (pintype "passive"))
      (node (ref "U1") (pin "2") (pinfunction "VOUT_2") (pintype "passive"))
      (node (ref "U1") (pin "4") (pinfunction "VOUT_4") (pintype "passive"))
      (node (ref "U11") (pin "1") (pinfunction "VBAT_1") (pintype "passive"))
      (node (ref "U11") (pin "24") (pinfunction "VDD_1_24") (pintype "passive"))
      (node (ref "U11") (pin "36") (pinfunction "VDD_2_36") (pintype "passive"))
      (node (ref "U11") (pin "48") (pinfunction "VDD_3_48") (pintype "passive"))
      (node (ref "U11") (pin "9") (pinfunction "VDDA_9") (pintype "passive"))
      (node (ref "U12") (pin "16") (pinfunction "VCC_16") (pintype "passive"))
      (node (ref "U13") (pin "13") (pinfunction "VDD_13") (pintype "passive"))
      (node (ref "U13") (pin "8") (pinfunction "VLOGIC_8") (pintype "passive"))
      (node (ref "U15") (pin "13") (pinfunction "VDDIO_13") (pintype "passive"))
      (node (ref "U15") (pin "2") (pinfunction "VDD_2") (pintype "passive"))
      (node (ref "U15") (pin "4") (pinfunction "S1_4") (pintype "passive"))
    )
    (net (code "49") (name "AGND") (class "Default")
      (node (ref "C10") (pin "2") (pinfunction "2_2") (pintype "passive"))
      (node (ref "C11") (pin "2") (pinfunction "2_2") (pintype "passive"))
      (node (ref "C12") (pin "1") (pinfunction "1_1") (pintype "passive"))
      (node (ref "C13") (pin "1") (pinfunction "1_1") (pintype "passive"))
      (node (ref "C14") (pin "2") (pinfunction "2_2") (pintype "passive"))
      (node (ref "C15") (pin "2") (pinfunction "2_2") (pintype "passive"))
      (node (ref "C5") (pin "1") (pinfunction "1_1") (pintype "passive"))
      (node (ref "C6") (pin "1") (pinfunction "1_1") (pintype "passive"))
      (node (ref "C7") (pin "2") (pinfunction "2_2") (pintype "passive"))
      (node (ref "C8") (pin "2") (pinfunction "2_2") (pintype "passive"))
      (node (ref "C9") (pin "2") (pinfunction "2_2") (pintype "passive"))
      (node (ref "D1") (pin "2") (pinfunction "2_2") (pintype "passive"))
      (node (ref "DC1") (pin "3") (pinfunction "3_3") (pintype "passive"))
      (node (ref "P1") (pin "2") (pinfunction "2_2") (pintype "passive"))
      (node (ref "P2") (pin "2") (pinfunction "2_2") (pintype "passive"))
      (node (ref "R1") (pin "1") (pinfunction "1_1") (pintype "passive"))
      (node (ref "R3") (pin "1") (pinfunction "1_1") (pintype "passive"))
      (node (ref "R4") (pin "1") (pinfunction "1_1") (pintype "passive"))
      (node (ref "R5") (pin "1") (pinfunction "1_1") (pintype "passive"))
      (node (ref "R6") (pin "1") (pinfunction "1_1") (pintype "passive"))
      (node (ref "R7") (pin "1") (pinfunction "1_1") (pintype "passive"))
      (node (ref "U10") (pin "1") (pinfunction "GND_1") (pintype "passive"))
      (node (ref "U10") (pin "9") (pinfunction "EP_9") (pintype "passive"))
      (node (ref "U2") (pin "1") (pinfunction "GND_1") (pintype "passive"))
      (node (ref "U3") (pin "1") (pinfunction "GND_1") (pintype "passive"))
      (node (ref "U3") (pin "9") (pinfunction "EP_9") (pintype "passive"))
      (node (ref "U4") (pin "1") (pinfunction "GND_1") (pintype "passive"))
      (node (ref "U4") (pin "9") (pinfunction "EP_9") (pintype "passive"))
      (node (ref "U5") (pin "1") (pinfunction "GND_1") (pintype "passive"))
      (node (ref "U5") (pin "9") (pinfunction "EP_9") (pintype "passive"))
      (node (ref "Vin") (pin "2") (pinfunction "C_2") (pintype "passive"))
    )
    (net (code "50") (name "DGND") (class "Default")
      (node (ref "3V3") (pin "2") (pinfunction "C_2") (pintype "passive"))
      (node (ref "5V") (pin "2") (pinfunction "C_2") (pintype "passive"))
      (node (ref "C1") (pin "2") (pinfunction "2_2") (pintype "passive"))
      (node (ref "C16") (pin "2") (pinfunction "2_2") (pintype "passive"))
      (node (ref "C17") (pin "2") (pinfunction "2_2") (pintype "passive"))
      (node (ref "C18") (pin "1") (pinfunction "1_1") (pintype "passive"))
      (node (ref "C19") (pin "1") (pinfunction "1_1") (pintype "passive"))
      (node (ref "C2") (pin "2") (pinfunction "2_2") (pintype "passive"))
      (node (ref "C21") (pin "1") (pinfunction "1_1") (pintype "passive"))
      (node (ref "C22") (pin "1") (pinfunction "1_1") (pintype "passive"))
      (node (ref "C23") (pin "1") (pinfunction "1_1") (pintype "passive"))
      (node (ref "C24") (pin "1") (pinfunction "1_1") (pintype "passive"))
      (node (ref "C25") (pin "1") (pinfunction "1_1") (pintype "passive"))
      (node (ref "C26") (pin "1") (pinfunction "1_1") (pintype "passive"))
      (node (ref "C28") (pin "1") (pinfunction "1_1") (pintype "passive"))
      (node (ref "C29") (pin "2") (pinfunction "2_2") (pintype "passive"))
      (node (ref "C30") (pin "2") (pinfunction "2_2") (pintype "passive"))
      (node (ref "C31") (pin "2") (pinfunction "2_2") (pintype "passive"))
      (node (ref "C32") (pin "2") (pinfunction "2_2") (pintype "passive"))
      (node (ref "C33") (pin "1") (pinfunction "1_1") (pintype "passive"))
      (node (ref "C34") (pin "2") (pinfunction "2_2") (pintype "passive"))
      (node (ref "C35") (pin "1") (pinfunction "1_1") (pintype "passive"))
      (node (ref "C36") (pin "1") (pinfunction "1_1") (pintype "passive"))
      (node (ref "C37") (pin "2") (pinfunction "2_2") (pintype "passive"))
      (node (ref "C38") (pin "1") (pinfunction "1_1") (pintype "passive"))
      (node (ref "C39") (pin "2") (pinfunction "2_2") (pintype "passive"))
      (node (ref "C4") (pin "1") (pinfunction "1_1") (pintype "passive"))
      (node (ref "CN1") (pin "3") (pinfunction "3_3") (pintype "passive"))
      (node (ref "CN1") (pin "4") (pinfunction "4_4") (pintype "passive"))
      (node (ref "CN10") (pin "4") (pinfunction "4_4") (pintype "passive"))
      (node (ref "CN3") (pin "2") (pinfunction "2_2") (pintype "passive"))
      (node (ref "CN4") (pin "2") (pinfunction "2_2") (pintype "passive"))
      (node (ref "CN5") (pin "2") (pinfunction "2_2") (pintype "passive"))
      (node (ref "CN6") (pin "2") (pinfunction "2_2") (pintype "passive"))
      (node (ref "CN7") (pin "4") (pinfunction "4_4") (pintype "passive"))
      (node (ref "CN8") (pin "4") (pinfunction "4_4") (pintype "passive"))
      (node (ref "KEY0") (pin "1") (pinfunction "1_1") (pintype "passive"))
      (node (ref "LED0") (pin "2") (pinfunction "C_2") (pintype "passive"))
      (node (ref "LED1") (pin "2") (pinfunction "C_2") (pintype "passive"))
      (node (ref "R1") (pin "2") (pinfunction "2_2") (pintype "passive"))
      (node (ref "R10") (pin "2") (pinfunction "2_2") (pintype "passive"))
      (node (ref "R8") (pin "2") (pinfunction "2_2") (pintype "passive"))
      (node (ref "RESET") (pin "1") (pinfunction "1_1") (pintype "passive"))
      (node (ref "SWD") (pin "4") (pinfunction "4_4") (pintype "passive"))
      (node (ref "U1") (pin "1") (pinfunction "ADJ/GND_1") (pintype "passive"))
      (node (ref "U11") (pin "23") (pinfunction "VSS_1_23") (pintype "passive"))
      (node (ref "U11") (pin "35") (pinfunction "VSS_2_35") (pintype "passive"))
      (node (ref "U11") (pin "47") (pinfunction "VSS_3_47") (pintype "passive"))
      (node (ref "U11") (pin "8") (pinfunction "VSSA_8") (pintype "passive"))
      (node (ref "U12") (pin "15") (pinfunction "GND_15") (pintype "passive"))
      (node (ref "U13") (pin "1") (pinfunction "CLKIN_1") (pintype "passive"))
      (node (ref "U13") (pin "11") (pinfunction "FSYNC_11") (pintype "passive"))
      (node (ref "U13") (pin "18") (pinfunction "GND_18") (pintype "passive"))
      (node (ref "U13") (pin "9") (pinfunction "AD0_9") (pintype "passive"))
      (node (ref "U14") (pin "1") (pinfunction "GND_1") (pintype "passive"))
      (node (ref "U15") (pin "11") (pinfunction "GND_11") (pintype "passive"))
      (node (ref "U15") (pin "9") (pinfunction "GND_9") (pintype "passive"))
      (node (ref "USB1") (pin "4") (pinfunction "ID_4") (pintype "passive"))
      (node (ref "USB1") (pin "5") (pinfunction "GND_5") (pintype "passive"))
      (node (ref "USB1") (pin "6") (pinfunction "6_6") (pintype "passive"))
      (node (ref "X2") (pin "2") (pinfunction "GND_2") (pintype "passive"))
      (node (ref "X2") (pin "4") (pinfunction "GND_4") (pintype "passive"))
    )
    (net (code "51") (name "Net-(3V3-A)") (class "Default")
      (node (ref "3V3") (pin "1") (pinfunction "A_1") (pintype "passive"))
      (node (ref "R14") (pin "1") (pinfunction "1_1") (pintype "passive"))
    )
    (net (code "52") (name "Net-(5V-A)") (class "Default")
      (node (ref "5V") (pin "1") (pinfunction "A_1") (pintype "passive"))
      (node (ref "R13") (pin "1") (pinfunction "1_1") (pintype "passive"))
    )
    (net (code "53") (name "Net-(D1-Pad1)") (class "Default")
      (node (ref "D1") (pin "1") (pinfunction "1_1") (pintype "passive"))
      (node (ref "L1") (pin "2") (pinfunction "2_2") (pintype "passive"))
      (node (ref "U2") (pin "3") (pinfunction "SW_3") (pintype "passive"))
      (node (ref "U2") (pin "6") (pinfunction "SW_6") (pintype "passive"))
    )
    (net (code "54") (name "Net-(LED0-A)") (class "Default")
      (node (ref "LED0") (pin "1") (pinfunction "A_1") (pintype "passive"))
      (node (ref "R16") (pin "1") (pinfunction "1_1") (pintype "passive"))
    )
    (net (code "55") (name "Net-(LED1-A)") (class "Default")
      (node (ref "LED1") (pin "1") (pinfunction "A_1") (pintype "passive"))
      (node (ref "R17") (pin "1") (pinfunction "1_1") (pintype "passive"))
    )
    (net (code "56") (name "Net-(U2-FB)") (class "Default")
      (node (ref "C3") (pin "1") (pinfunction "1_1") (pintype "passive"))
      (node (ref "R2") (pin "2") (pinfunction "2_2") (pintype "passive"))
      (node (ref "R5") (pin "2") (pinfunction "2_2") (pintype "passive"))
      (node (ref "U2") (pin "2") (pinfunction "FB_2") (pintype "passive"))
    )
    (net (code "57") (name "Net-(U3-LSS)") (class "Default")
      (node (ref "R3") (pin "2") (pinfunction "2_2") (pintype "passive"))
      (node (ref "U3") (pin "7") (pinfunction "LSS_7") (pintype "passive"))
    )
    (net (code "58") (name "Net-(U4-LSS)") (class "Default")
      (node (ref "R4") (pin "2") (pinfunction "2_2") (pintype "passive"))
      (node (ref "U4") (pin "7") (pinfunction "LSS_7") (pintype "passive"))
    )
    (net (code "59") (name "Net-(U5-LSS)") (class "Default")
      (node (ref "R6") (pin "2") (pinfunction "2_2") (pintype "passive"))
      (node (ref "U5") (pin "7") (pinfunction "LSS_7") (pintype "passive"))
    )
    (net (code "60") (name "Net-(U10-LSS)") (class "Default")
      (node (ref "R7") (pin "2") (pinfunction "2_2") (pintype "passive"))
      (node (ref "U10") (pin "7") (pinfunction "LSS_7") (pintype "passive"))
    )
    (net (code "61") (name "Net-(U11-BOOT0)") (class "Default")
      (node (ref "R8") (pin "1") (pinfunction "1_1") (pintype "passive"))
      (node (ref "U11") (pin "44") (pinfunction "BOOT0_44") (pintype "passive"))
    )
    (net (code "62") (name "Net-(U11-NRST)") (class "Default")
      (node (ref "C18") (pin "2") (pinfunction "2_2") (pintype "passive"))
      (node (ref "R9") (pin "1") (pinfunction "1_1") (pintype "passive"))
      (node (ref "RESET") (pin "2") (pinfunction "2_2") (pintype "passive"))
      (node (ref "U11") (pin "7") (pinfunction "NRST_7") (pintype "passive"))
    )
    (net (code "63") (name "Net-(U12-C1+)") (class "Default")
      (node (ref "C20") (pin "1") (pinfunction "1_1") (pintype "passive"))
      (node (ref "U12") (pin "1") (pinfunction "C1+_1") (pintype "passive"))
    )
    (net (code "64") (name "Net-(U12-C1-)") (class "Default")
      (node (ref "C20") (pin "2") (pinfunction "2_2") (pintype "passive"))
      (node (ref "U12") (pin "3") (pinfunction "C1-_3") (pintype "passive"))
    )
    (net (code "65") (name "Net-(U12-C2+)") (class "Default")
      (node (ref "C27") (pin "1") (pinfunction "1_1") (pintype "passive"))
      (node (ref "U12") (pin "4") (pinfunction "C2+_4") (pintype "passive"))
    )
    (net (code "66") (name "Net-(U12-C2-)") (class "Default")
      (node (ref "C27") (pin "2") (pinfunction "2_2") (pintype "passive"))
      (node (ref "U12") (pin "5") (pinfunction "C2-_5") (pintype "passive"))
    )
    (net (code "67") (name "Net-(U12-V+)") (class "Default")
      (node (ref "C19") (pin "2") (pinfunction "2_2") (pintype "passive"))
      (node (ref "U12") (pin "2") (pinfunction "V+_2") (pintype "passive"))
    )
    (net (code "68") (name "Net-(U12-V-)") (class "Default")
      (node (ref "C29") (pin "1") (pinfunction "1_1") (pintype "passive"))
      (node (ref "U12") (pin "6") (pinfunction "V-_6") (pintype "passive"))
    )
    (net (code "69") (name "Net-(U13-CPOUT)") (class "Default")
      (node (ref "C32") (pin "1") (pinfunction "1_1") (pintype "passive"))
      (node (ref "U13") (pin "20") (pinfunction "CPOUT_20") (pintype "passive"))
    )
    (net (code "70") (name "Net-(U13-REGOUT)") (class "Default")
      (node (ref "C35") (pin "2") (pinfunction "2_2") (pintype "passive"))
      (node (ref "U13") (pin "10") (pinfunction "REGOUT_10") (pintype "passive"))
    )
    (net (code "71") (name "Net-(U14-V3)") (class "Default")
      (node (ref "C31") (pin "1") (pinfunction "1_1") (pintype "passive"))
      (node (ref "U14") (pin "4") (pinfunction "V3_4") (pintype "passive"))
    )
    (net (code "72") (name "Net-(U14-XI)") (class "Default")
      (node (ref "C38") (pin "2") (pinfunction "2_2") (pintype "passive"))
      (node (ref "U14") (pin "7") (pinfunction "XI_7") (pintype "passive"))
      (node (ref "X2") (pin "3") (pinfunction "OSC2_3") (pintype "passive"))
    )
    (net (code "73") (name "Net-(U14-XO)") (class "Default")
      (node (ref "C39") (pin "1") (pinfunction "1_1") (pintype "passive"))
      (node (ref "U14") (pin "8") (pinfunction "XO_8") (pintype "passive"))
      (node (ref "X2") (pin "1") (pinfunction "OSC1_1") (pintype "passive"))
    )
    (net (code "74") (name "Net-(U15-C1)") (class "Default")
      (node (ref "C34") (pin "1") (pinfunction "1_1") (pintype "passive"))
      (node (ref "U15") (pin "10") (pinfunction "C1_10") (pintype "passive"))
    )
    (net (code "75") (name "Net-(U15-SETC)") (class "Default")
      (node (ref "C40") (pin "2") (pinfunction "2_2") (pintype "passive"))
      (node (ref "U15") (pin "12") (pinfunction "SETC_12") (pintype "passive"))
    )
    (net (code "76") (name "Net-(U15-SETP)") (class "Default")
      (node (ref "C40") (pin "1") (pinfunction "1_1") (pintype "passive"))
      (node (ref "U15") (pin "8") (pinfunction "SETP_8") (pintype "passive"))
    )
    (net (code "77") (name "Net-(Vin-A)") (class "Default")
      (node (ref "R12") (pin "1") (pinfunction "1_1") (pintype "passive"))
      (node (ref "Vin") (pin "1") (pinfunction "A_1") (pintype "passive"))
    )
    (net (code "78") (name "VIN_OPEN") (class "Default")
      (node (ref "C10") (pin "1") (pinfunction "1_1") (pintype "passive"))
      (node (ref "C12") (pin "2") (pinfunction "2_2") (pintype "passive"))
      (node (ref "C13") (pin "2") (pinfunction "2_2") (pintype "passive"))
      (node (ref "C14") (pin "1") (pinfunction "1_1") (pintype "passive"))
      (node (ref "C15") (pin "1") (pinfunction "1_1") (pintype "passive"))
      (node (ref "C5") (pin "2") (pinfunction "2_2") (pintype "passive"))
      (node (ref "C6") (pin "2") (pinfunction "2_2") (pintype "passive"))
      (node (ref "C7") (pin "1") (pinfunction "1_1") (pintype "passive"))
      (node (ref "C8") (pin "1") (pinfunction "1_1") (pintype "passive"))
      (node (ref "C9") (pin "1") (pinfunction "1_1") (pintype "passive"))
      (node (ref "R12") (pin "2") (pinfunction "2_2") (pintype "passive"))
      (node (ref "SW1") (pin "1") (pinfunction "1_1") (pintype "passive"))
      (node (ref "U10") (pin "5") (pinfunction "VBB_5") (pintype "passive"))
      (node (ref "U2") (pin "4") (pinfunction "EN_4") (pintype "passive"))
      (node (ref "U2") (pin "5") (pinfunction "VIN_5") (pintype "passive"))
      (node (ref "U3") (pin "5") (pinfunction "VBB_5") (pintype "passive"))
      (node (ref "U4") (pin "5") (pinfunction "VBB_5") (pintype "passive"))
      (node (ref "U5") (pin "5") (pinfunction "VBB_5") (pintype "passive"))
    )
    (net (code "79") (name "VOUT_5V{slash}5A") (class "Default")
      (node (ref "C1") (pin "1") (pinfunction "1_1") (pintype "passive"))
      (node (ref "C11") (pin "1") (pinfunction "1_1") (pintype "passive"))
      (node (ref "C2") (pin "1") (pinfunction "1_1") (pintype "passive"))
      (node (ref "C3") (pin "2") (pinfunction "2_2") (pintype "passive"))
      (node (ref "C30") (pin "1") (pinfunction "1_1") (pintype "passive"))
      (node (ref "CN1") (pin "1") (pinfunction "1_1") (pintype "passive"))
      (node (ref "CN1") (pin "2") (pinfunction "2_2") (pintype "passive"))
      (node (ref "CN10") (pin "1") (pinfunction "1_1") (pintype "passive"))
      (node (ref "CN3") (pin "5") (pinfunction "5_5") (pintype "passive"))
      (node (ref "CN4") (pin "5") (pinfunction "5_5") (pintype "passive"))
      (node (ref "CN5") (pin "5") (pinfunction "5_5") (pintype "passive"))
      (node (ref "CN6") (pin "5") (pinfunction "5_5") (pintype "passive"))
      (node (ref "CN7") (pin "1") (pinfunction "1_1") (pintype "passive"))
      (node (ref "CN8") (pin "1") (pinfunction "1_1") (pintype "passive"))
      (node (ref "L1") (pin "1") (pinfunction "1_1") (pintype "passive"))
      (node (ref "P2") (pin "1") (pinfunction "1_1") (pintype "passive"))
      (node (ref "R13") (pin "2") (pinfunction "2_2") (pintype "passive"))
      (node (ref "R2") (pin "1") (pinfunction "1_1") (pintype "passive"))
      (node (ref "SWD") (pin "1") (pinfunction "1_1") (pintype "passive"))
      (node (ref "U1") (pin "3") (pinfunction "VIN_3") (pintype "passive"))
      (node (ref "U10") (pin "4") (pinfunction "VREF_4") (pintype "passive"))
      (node (ref "U14") (pin "16") (pinfunction "VCC_16") (pintype "passive"))
      (node (ref "U3") (pin "4") (pinfunction "VREF_4") (pintype "passive"))
      (node (ref "U4") (pin "4") (pinfunction "VREF_4") (pintype "passive"))
      (node (ref "U5") (pin "4") (pinfunction "VREF_4") (pintype "passive"))
    )
    (net (code "80") (name "unconnected-(DC1-Pad2)") (class "Default")
      (node (ref "DC1") (pin "2") (pinfunction "2_2") (pintype "passive+no_connect"))
    )
    (net (code "81") (name "unconnected-(SW1-Pad3)") (class "Default")
      (node (ref "SW1") (pin "3") (pinfunction "3_3") (pintype "passive+no_connect"))
    )
    (net (code "82") (name "unconnected-(U6-Pad1)") (class "Default")
      (node (ref "U6") (pin "1") (pinfunction "1_1") (pintype "passive+no_connect"))
    )
    (net (code "83") (name "unconnected-(U7-Pad1)") (class "Default")
      (node (ref "U7") (pin "1") (pinfunction "1_1") (pintype "passive+no_connect"))
    )
    (net (code "84") (name "unconnected-(U8-Pad1)") (class "Default")
      (node (ref "U8") (pin "1") (pinfunction "1_1") (pintype "passive+no_connect"))
    )
    (net (code "85") (name "unconnected-(U9-Pad1)") (class "Default")
      (node (ref "U9") (pin "1") (pinfunction "1_1") (pintype "passive+no_connect"))
    )
    (net (code "86") (name "unconnected-(U11-PC13-TAMPER-RTC-Pad2)") (class "Default")
      (node (ref "U11") (pin "2") (pinfunction "PC13-TAMPER-RTC_2") (pintype "passive+no_connect"))
    )
    (net (code "87") (name "unconnected-(U11-PC14-OSC32_IN-Pad3)") (class "Default")
      (node (ref "U11") (pin "3") (pinfunction "PC14-OSC32_IN_3") (pintype "passive+no_connect"))
    )
    (net (code "88") (name "unconnected-(U11-PC15-OSC32_OUT-Pad4)") (class "Default")
      (node (ref "U11") (pin "4") (pinfunction "PC15-OSC32_OUT_4") (pintype "passive+no_connect"))
    )
    (net (code "89") (name "unconnected-(U12-RXIN2-Pad8)") (class "Default")
      (node (ref "U12") (pin "8") (pinfunction "RXIN2_8") (pintype "passive+no_connect"))
    )
    (net (code "90") (name "unconnected-(U12-RXOUT2#-Pad9)") (class "Default")
      (node (ref "U12") (pin "9") (pinfunction "RXOUT2#_9") (pintype "passive+no_connect"))
    )
    (net (code "91") (name "unconnected-(U12-TXIN2-Pad10)") (class "Default")
      (node (ref "U12") (pin "10") (pinfunction "TXIN2_10") (pintype "passive+no_connect"))
    )
    (net (code "92") (name "unconnected-(U12-TXOUT2#-Pad7)") (class "Default")
      (node (ref "U12") (pin "7") (pinfunction "TXOUT2#_7") (pintype "passive+no_connect"))
    )
    (net (code "93") (name "unconnected-(U13-AUX_CL-Pad7)") (class "Default")
      (node (ref "U13") (pin "7") (pinfunction "AUX_CL_7") (pintype "passive+no_connect"))
    )
    (net (code "94") (name "unconnected-(U13-AUX_DA-Pad6)") (class "Default")
      (node (ref "U13") (pin "6") (pinfunction "AUX_DA_6") (pintype "passive+no_connect"))
    )
    (net (code "95") (name "unconnected-(U13-EP-Pad25)") (class "Default")
      (node (ref "U13") (pin "25") (pinfunction "EP_25") (pintype "passive+no_connect"))
    )
    (net (code "96") (name "unconnected-(U13-NC-Pad2)") (class "Default")
      (node (ref "U13") (pin "2") (pinfunction "NC_2") (pintype "passive+no_connect"))
    )
    (net (code "97") (name "unconnected-(U13-NC-Pad3)") (class "Default")
      (node (ref "U13") (pin "3") (pinfunction "NC_3") (pintype "passive+no_connect"))
    )
    (net (code "98") (name "unconnected-(U13-NC-Pad4)") (class "Default")
      (node (ref "U13") (pin "4") (pinfunction "NC_4") (pintype "passive+no_connect"))
    )
    (net (code "99") (name "unconnected-(U13-NC-Pad5)") (class "Default")
      (node (ref "U13") (pin "5") (pinfunction "NC_5") (pintype "passive+no_connect"))
    )
    (net (code "100") (name "unconnected-(U13-NC-Pad14)") (class "Default")
      (node (ref "U13") (pin "14") (pinfunction "NC_14") (pintype "passive+no_connect"))
    )
    (net (code "101") (name "unconnected-(U13-NC-Pad15)") (class "Default")
      (node (ref "U13") (pin "15") (pinfunction "NC_15") (pintype "passive+no_connect"))
    )
    (net (code "102") (name "unconnected-(U13-NC-Pad16)") (class "Default")
      (node (ref "U13") (pin "16") (pinfunction "NC_16") (pintype "passive+no_connect"))
    )
    (net (code "103") (name "unconnected-(U13-NC-Pad17)") (class "Default")
      (node (ref "U13") (pin "17") (pinfunction "NC_17") (pintype "passive+no_connect"))
    )
    (net (code "104") (name "unconnected-(U13-RESV-Pad19)") (class "Default")
      (node (ref "U13") (pin "19") (pinfunction "RESV_19") (pintype "passive+no_connect"))
    )
    (net (code "105") (name "unconnected-(U13-RESV-Pad21)") (class "Default")
      (node (ref "U13") (pin "21") (pinfunction "RESV_21") (pintype "passive+no_connect"))
    )
    (net (code "106") (name "unconnected-(U13-RESV-Pad22)") (class "Default")
      (node (ref "U13") (pin "22") (pinfunction "RESV_22") (pintype "passive+no_connect"))
    )
    (net (code "107") (name "unconnected-(U14-CTS#-Pad9)") (class "Default")
      (node (ref "U14") (pin "9") (pinfunction "CTS#_9") (pintype "passive+no_connect"))
    )
    (net (code "108") (name "unconnected-(U14-DCD#-Pad12)") (class "Default")
      (node (ref "U14") (pin "12") (pinfunction "DCD#_12") (pintype "passive+no_connect"))
    )
    (net (code "109") (name "unconnected-(U14-DSR#-Pad10)") (class "Default")
      (node (ref "U14") (pin "10") (pinfunction "DSR#_10") (pintype "passive+no_connect"))
    )
    (net (code "110") (name "unconnected-(U14-DTR#-Pad13)") (class "Default")
      (node (ref "U14") (pin "13") (pinfunction "DTR#_13") (pintype "passive+no_connect"))
    )
    (net (code "111") (name "unconnected-(U14-R232-Pad15)") (class "Default")
      (node (ref "U14") (pin "15") (pinfunction "R232_15") (pintype "passive+no_connect"))
    )
    (net (code "112") (name "unconnected-(U14-RI-Pad11)") (class "Default")
      (node (ref "U14") (pin "11") (pinfunction "RI_11") (pintype "passive+no_connect"))
    )
    (net (code "113") (name "unconnected-(U14-RTS#-Pad14)") (class "Default")
      (node (ref "U14") (pin "14") (pinfunction "RTS#_14") (pintype "passive+no_connect"))
    )
    (net (code "114") (name "unconnected-(U15-NC-Pad3)") (class "Default")
      (node (ref "U15") (pin "3") (pinfunction "NC_3") (pintype "passive+no_connect"))
    )
    (net (code "115") (name "unconnected-(U15-NC-Pad5)") (class "Default")
      (node (ref "U15") (pin "5") (pinfunction "NC_5") (pintype "passive+no_connect"))
    )
    (net (code "116") (name "unconnected-(U15-NC-Pad6)") (class "Default")
      (node (ref "U15") (pin "6") (pinfunction "NC_6") (pintype "passive+no_connect"))
    )
    (net (code "117") (name "unconnected-(U15-NC-Pad7)") (class "Default")
      (node (ref "U15") (pin "7") (pinfunction "NC_7") (pintype "passive+no_connect"))
    )
    (net (code "118") (name "unconnected-(U15-NC-Pad14)") (class "Default")
      (node (ref "U15") (pin "14") (pinfunction "NC_14") (pintype "passive+no_connect"))
    )
    (net (code "119") (name "unconnected-(USB1-VBUS-Pad1)") (class "Default")
      (node (ref "USB1") (pin "1") (pinfunction "VBUS_1") (pintype "passive"))
    )
  )
)
